# buttonInput.net
KiCad netlist of a schematic drawn in Altium Designer
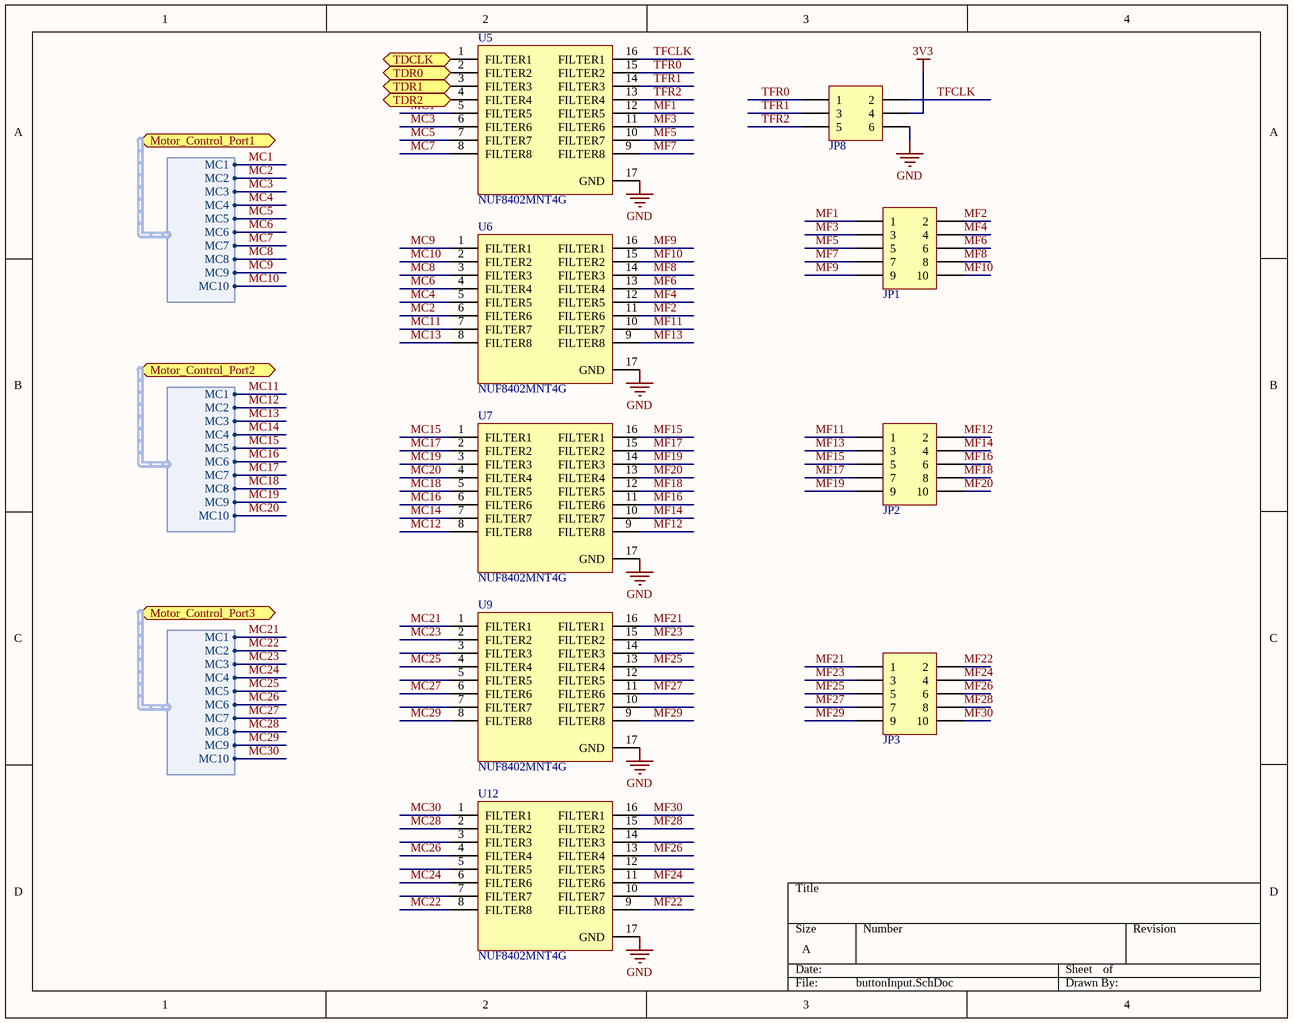
[diagram p0: buttonInput.SchDoc]

(export (version "E")
  (design (tool "Eeschema 10.0.6"))
  (components
    (comp (ref "JP1")
      (value "Header 5x2 2.54mm")
      (footprint "2X5")
      (description "Header, 8-Pin")
      (libsource (lib "HSBNE-Vend") (part "Header 5x2"))
    )
    (comp (ref "JP2")
      (value "Header 5x2 2.54mm")
      (footprint "2X5")
      (description "Header, 8-Pin")
      (libsource (lib "HSBNE-Vend") (part "Header 5x2"))
    )
    (comp (ref "JP3")
      (value "Header 5x2 2.54mm")
      (footprint "2X5")
      (description "Header, 8-Pin")
      (libsource (lib "HSBNE-Vend") (part "Header 5x2"))
    )
    (comp (ref "JP8")
      (value "Header 3x2 2.54mm")
      (footprint "2X3")
      (description "Header, 6-Pin")
      (libsource (lib "HSBNE-Vend") (part "Header 3x2"))
    )
    (comp (ref "U5")
      (value "NUF8402MNT4G")
      (footprint "ONSC-DFN-16-506AC_V")
      (fields (field (name "MANUFACTURER") "On Semiconductor"))
      (libsource (lib "Altium Content Vault") (part "ONSC-EMI-NUF8XXX-16"))
    )
    (comp (ref "U6")
      (value "NUF8402MNT4G")
      (footprint "ONSC-DFN-16-506AC_V")
      (fields (field (name "MANUFACTURER") "On Semiconductor"))
      (libsource (lib "Altium Content Vault") (part "ONSC-EMI-NUF8XXX-16"))
    )
    (comp (ref "U7")
      (value "NUF8402MNT4G")
      (footprint "ONSC-DFN-16-506AC_V")
      (fields (field (name "MANUFACTURER") "On Semiconductor"))
      (libsource (lib "Altium Content Vault") (part "ONSC-EMI-NUF8XXX-16"))
    )
    (comp (ref "U9")
      (value "NUF8402MNT4G")
      (footprint "ONSC-DFN-16-506AC_V")
      (fields (field (name "MANUFACTURER") "On Semiconductor"))
      (libsource (lib "Altium Content Vault") (part "ONSC-EMI-NUF8XXX-16"))
    )
    (comp (ref "U12")
      (value "NUF8402MNT4G")
      (footprint "ONSC-DFN-16-506AC_V")
      (fields (field (name "MANUFACTURER") "On Semiconductor"))
      (libsource (lib "Altium Content Vault") (part "ONSC-EMI-NUF8XXX-16"))
    )
  )
  (nets
    (net (code "2") (name "/MC1") (class "Default")
      (node (ref "U5") (pin "5") (pinfunction "FILTER5_5") (pintype "passive"))
    )
    (net (code "3") (name "/MC2") (class "Default")
      (node (ref "U6") (pin "6") (pinfunction "FILTER6_6") (pintype "passive"))
    )
    (net (code "4") (name "/MC3") (class "Default")
      (node (ref "U5") (pin "6") (pinfunction "FILTER6_6") (pintype "passive"))
    )
    (net (code "5") (name "/MC4") (class "Default")
      (node (ref "U6") (pin "5") (pinfunction "FILTER5_5") (pintype "passive"))
    )
    (net (code "6") (name "/MC5") (class "Default")
      (node (ref "U5") (pin "7") (pinfunction "FILTER7_7") (pintype "passive"))
    )
    (net (code "7") (name "/MC6") (class "Default")
      (node (ref "U6") (pin "4") (pinfunction "FILTER4_4") (pintype "passive"))
    )
    (net (code "8") (name "/MC7") (class "Default")
      (node (ref "U5") (pin "8") (pinfunction "FILTER8_8") (pintype "passive"))
    )
    (net (code "9") (name "/MC8") (class "Default")
      (node (ref "U6") (pin "3") (pinfunction "FILTER3_3") (pintype "passive"))
    )
    (net (code "10") (name "/MC9") (class "Default")
      (node (ref "U6") (pin "1") (pinfunction "FILTER1_1") (pintype "passive"))
    )
    (net (code "11") (name "/MC10") (class "Default")
      (node (ref "U6") (pin "2") (pinfunction "FILTER2_2") (pintype "passive"))
    )
    (net (code "12") (name "/MC11") (class "Default")
      (node (ref "U6") (pin "7") (pinfunction "FILTER7_7") (pintype "passive"))
    )
    (net (code "13") (name "/MC12") (class "Default")
      (node (ref "U7") (pin "8") (pinfunction "FILTER8_8") (pintype "passive"))
    )
    (net (code "14") (name "/MC13") (class "Default")
      (node (ref "U6") (pin "8") (pinfunction "FILTER8_8") (pintype "passive"))
    )
    (net (code "15") (name "/MC14") (class "Default")
      (node (ref "U7") (pin "7") (pinfunction "FILTER7_7") (pintype "passive"))
    )
    (net (code "16") (name "/MC15") (class "Default")
      (node (ref "U7") (pin "1") (pinfunction "FILTER1_1") (pintype "passive"))
    )
    (net (code "17") (name "/MC16") (class "Default")
      (node (ref "U7") (pin "6") (pinfunction "FILTER6_6") (pintype "passive"))
    )
    (net (code "18") (name "/MC17") (class "Default")
      (node (ref "U7") (pin "2") (pinfunction "FILTER2_2") (pintype "passive"))
    )
    (net (code "19") (name "/MC18") (class "Default")
      (node (ref "U7") (pin "5") (pinfunction "FILTER5_5") (pintype "passive"))
    )
    (net (code "20") (name "/MC19") (class "Default")
      (node (ref "U7") (pin "3") (pinfunction "FILTER3_3") (pintype "passive"))
    )
    (net (code "21") (name "/MC20") (class "Default")
      (node (ref "U7") (pin "4") (pinfunction "FILTER4_4") (pintype "passive"))
    )
    (net (code "22") (name "/MC21") (class "Default")
      (node (ref "U9") (pin "1") (pinfunction "FILTER1_1") (pintype "passive"))
    )
    (net (code "23") (name "/MC22") (class "Default")
      (node (ref "U12") (pin "8") (pinfunction "FILTER8_8") (pintype "passive"))
    )
    (net (code "24") (name "/MC23") (class "Default")
      (node (ref "U9") (pin "2") (pinfunction "FILTER2_2") (pintype "passive"))
    )
    (net (code "25") (name "/MC24") (class "Default")
      (node (ref "U12") (pin "6") (pinfunction "FILTER6_6") (pintype "passive"))
    )
    (net (code "26") (name "/MC25") (class "Default")
      (node (ref "U9") (pin "4") (pinfunction "FILTER4_4") (pintype "passive"))
    )
    (net (code "27") (name "/MC26") (class "Default")
      (node (ref "U12") (pin "4") (pinfunction "FILTER4_4") (pintype "passive"))
    )
    (net (code "28") (name "/MC27") (class "Default")
      (node (ref "U9") (pin "6") (pinfunction "FILTER6_6") (pintype "passive"))
    )
    (net (code "29") (name "/MC28") (class "Default")
      (node (ref "U12") (pin "2") (pinfunction "FILTER2_2") (pintype "passive"))
    )
    (net (code "30") (name "/MC29") (class "Default")
      (node (ref "U9") (pin "8") (pinfunction "FILTER8_8") (pintype "passive"))
    )
    (net (code "31") (name "/MC30") (class "Default")
      (node (ref "U12") (pin "1") (pinfunction "FILTER1_1") (pintype "passive"))
    )
    (net (code "32") (name "/MF1") (class "Default")
      (node (ref "JP1") (pin "1") (pinfunction "1_1") (pintype "passive"))
      (node (ref "U5") (pin "12") (pinfunction "FILTER5_12") (pintype "passive"))
    )
    (net (code "33") (name "/MF2") (class "Default")
      (node (ref "JP1") (pin "2") (pinfunction "2_2") (pintype "passive"))
      (node (ref "U6") (pin "11") (pinfunction "FILTER6_11") (pintype "passive"))
    )
    (net (code "34") (name "/MF3") (class "Default")
      (node (ref "JP1") (pin "3") (pinfunction "3_3") (pintype "passive"))
      (node (ref "U5") (pin "11") (pinfunction "FILTER6_11") (pintype "passive"))
    )
    (net (code "35") (name "/MF4") (class "Default")
      (node (ref "JP1") (pin "4") (pinfunction "4_4") (pintype "passive"))
      (node (ref "U6") (pin "12") (pinfunction "FILTER5_12") (pintype "passive"))
    )
    (net (code "36") (name "/MF5") (class "Default")
      (node (ref "JP1") (pin "5") (pinfunction "5_5") (pintype "passive"))
      (node (ref "U5") (pin "10") (pinfunction "FILTER7_10") (pintype "passive"))
    )
    (net (code "37") (name "/MF6") (class "Default")
      (node (ref "JP1") (pin "6") (pinfunction "6_6") (pintype "passive"))
      (node (ref "U6") (pin "13") (pinfunction "FILTER4_13") (pintype "passive"))
    )
    (net (code "38") (name "/MF7") (class "Default")
      (node (ref "JP1") (pin "7") (pinfunction "7_7") (pintype "passive"))
      (node (ref "U5") (pin "9") (pinfunction "FILTER8_9") (pintype "passive"))
    )
    (net (code "39") (name "/MF8") (class "Default")
      (node (ref "JP1") (pin "8") (pinfunction "8_8") (pintype "passive"))
      (node (ref "U6") (pin "14") (pinfunction "FILTER3_14") (pintype "passive"))
    )
    (net (code "40") (name "/MF9") (class "Default")
      (node (ref "JP1") (pin "9") (pinfunction "9_9") (pintype "passive"))
      (node (ref "U6") (pin "16") (pinfunction "FILTER1_16") (pintype "passive"))
    )
    (net (code "41") (name "/MF10") (class "Default")
      (node (ref "JP1") (pin "10") (pinfunction "10_10") (pintype "passive"))
      (node (ref "U6") (pin "15") (pinfunction "FILTER2_15") (pintype "passive"))
    )
    (net (code "42") (name "/MF11") (class "Default")
      (node (ref "JP2") (pin "1") (pinfunction "1_1") (pintype "passive"))
      (node (ref "U6") (pin "10") (pinfunction "FILTER7_10") (pintype "passive"))
    )
    (net (code "43") (name "/MF12") (class "Default")
      (node (ref "JP2") (pin "2") (pinfunction "2_2") (pintype "passive"))
      (node (ref "U7") (pin "9") (pinfunction "FILTER8_9") (pintype "passive"))
    )
    (net (code "44") (name "/MF13") (class "Default")
      (node (ref "JP2") (pin "3") (pinfunction "3_3") (pintype "passive"))
      (node (ref "U6") (pin "9") (pinfunction "FILTER8_9") (pintype "passive"))
    )
    (net (code "45") (name "/MF14") (class "Default")
      (node (ref "JP2") (pin "4") (pinfunction "4_4") (pintype "passive"))
      (node (ref "U7") (pin "10") (pinfunction "FILTER7_10") (pintype "passive"))
    )
    (net (code "46") (name "/MF15") (class "Default")
      (node (ref "JP2") (pin "5") (pinfunction "5_5") (pintype "passive"))
      (node (ref "U7") (pin "16") (pinfunction "FILTER1_16") (pintype "passive"))
    )
    (net (code "47") (name "/MF16") (class "Default")
      (node (ref "JP2") (pin "6") (pinfunction "6_6") (pintype "passive"))
      (node (ref "U7") (pin "11") (pinfunction "FILTER6_11") (pintype "passive"))
    )
    (net (code "48") (name "/MF17") (class "Default")
      (node (ref "JP2") (pin "7") (pinfunction "7_7") (pintype "passive"))
      (node (ref "U7") (pin "15") (pinfunction "FILTER2_15") (pintype "passive"))
    )
    (net (code "49") (name "/MF18") (class "Default")
      (node (ref "JP2") (pin "8") (pinfunction "8_8") (pintype "passive"))
      (node (ref "U7") (pin "12") (pinfunction "FILTER5_12") (pintype "passive"))
    )
    (net (code "50") (name "/MF19") (class "Default")
      (node (ref "JP2") (pin "9") (pinfunction "9_9") (pintype "passive"))
      (node (ref "U7") (pin "14") (pinfunction "FILTER3_14") (pintype "passive"))
    )
    (net (code "51") (name "/MF20") (class "Default")
      (node (ref "JP2") (pin "10") (pinfunction "10_10") (pintype "passive"))
      (node (ref "U7") (pin "13") (pinfunction "FILTER4_13") (pintype "passive"))
    )
    (net (code "52") (name "/MF21") (class "Default")
      (node (ref "JP3") (pin "1") (pinfunction "1_1") (pintype "passive"))
      (node (ref "U9") (pin "16") (pinfunction "FILTER1_16") (pintype "passive"))
    )
    (net (code "53") (name "/MF22") (class "Default")
      (node (ref "JP3") (pin "2") (pinfunction "2_2") (pintype "passive"))
      (node (ref "U12") (pin "9") (pinfunction "FILTER8_9") (pintype "passive"))
    )
    (net (code "54") (name "/MF23") (class "Default")
      (node (ref "JP3") (pin "3") (pinfunction "3_3") (pintype "passive"))
      (node (ref "U9") (pin "15") (pinfunction "FILTER2_15") (pintype "passive"))
    )
    (net (code "55") (name "/MF24") (class "Default")
      (node (ref "JP3") (pin "4") (pinfunction "4_4") (pintype "passive"))
      (node (ref "U12") (pin "11") (pinfunction "FILTER6_11") (pintype "passive"))
    )
    (net (code "56") (name "/MF25") (class "Default")
      (node (ref "JP3") (pin "5") (pinfunction "5_5") (pintype "passive"))
      (node (ref "U9") (pin "13") (pinfunction "FILTER4_13") (pintype "passive"))
    )
    (net (code "57") (name "/MF26") (class "Default")
      (node (ref "JP3") (pin "6") (pinfunction "6_6") (pintype "passive"))
      (node (ref "U12") (pin "13") (pinfunction "FILTER4_13") (pintype "passive"))
    )
    (net (code "58") (name "/MF27") (class "Default")
      (node (ref "JP3") (pin "7") (pinfunction "7_7") (pintype "passive"))
      (node (ref "U9") (pin "11") (pinfunction "FILTER6_11") (pintype "passive"))
    )
    (net (code "59") (name "/MF28") (class "Default")
      (node (ref "JP3") (pin "8") (pinfunction "8_8") (pintype "passive"))
      (node (ref "U12") (pin "15") (pinfunction "FILTER2_15") (pintype "passive"))
    )
    (net (code "60") (name "/MF29") (class "Default")
      (node (ref "JP3") (pin "9") (pinfunction "9_9") (pintype "passive"))
      (node (ref "U9") (pin "9") (pinfunction "FILTER8_9") (pintype "passive"))
    )
    (net (code "61") (name "/MF30") (class "Default")
      (node (ref "JP3") (pin "10") (pinfunction "10_10") (pintype "passive"))
      (node (ref "U12") (pin "16") (pinfunction "FILTER1_16") (pintype "passive"))
    )
    (net (code "62") (name "/TDCLK") (class "Default")
      (node (ref "U5") (pin "1") (pinfunction "FILTER1_1") (pintype "passive"))
    )
    (net (code "63") (name "/TDR0") (class "Default")
      (node (ref "U5") (pin "2") (pinfunction "FILTER2_2") (pintype "passive"))
    )
    (net (code "64") (name "/TDR1") (class "Default")
      (node (ref "U5") (pin "3") (pinfunction "FILTER3_3") (pintype "passive"))
    )
    (net (code "65") (name "/TDR2") (class "Default")
      (node (ref "U5") (pin "4") (pinfunction "FILTER4_4") (pintype "passive"))
    )
    (net (code "66") (name "/TFCLK") (class "Default")
      (node (ref "JP8") (pin "2") (pinfunction "2_2") (pintype "passive"))
      (node (ref "U5") (pin "16") (pinfunction "FILTER1_16") (pintype "passive"))
    )
    (net (code "67") (name "/TFR0") (class "Default")
      (node (ref "JP8") (pin "1") (pinfunction "1_1") (pintype "passive"))
      (node (ref "U5") (pin "15") (pinfunction "FILTER2_15") (pintype "passive"))
    )
    (net (code "68") (name "/TFR1") (class "Default")
      (node (ref "JP8") (pin "3") (pinfunction "3_3") (pintype "passive"))
      (node (ref "U5") (pin "14") (pinfunction "FILTER3_14") (pintype "passive"))
    )
    (net (code "69") (name "/TFR2") (class "Default")
      (node (ref "JP8") (pin "5") (pinfunction "5_5") (pintype "passive"))
      (node (ref "U5") (pin "13") (pinfunction "FILTER4_13") (pintype "passive"))
    )
    (net (code "71") (name "3V3") (class "Default")
      (node (ref "JP8") (pin "4") (pinfunction "4_4") (pintype "passive"))
    )
    (net (code "72") (name "GND") (class "Default")
      (node (ref "JP8") (pin "6") (pinfunction "6_6") (pintype "passive"))
      (node (ref "U12") (pin "17") (pinfunction "GND_17") (pintype "power_in"))
      (node (ref "U5") (pin "17") (pinfunction "GND_17") (pintype "power_in"))
      (node (ref "U6") (pin "17") (pinfunction "GND_17") (pintype "power_in"))
      (node (ref "U7") (pin "17") (pinfunction "GND_17") (pintype "power_in"))
      (node (ref "U9") (pin "17") (pinfunction "GND_17") (pintype "power_in"))
    )
    (net (code "73") (name "unconnected-(U9-FILTER3-Pad3)") (class "Default")
      (node (ref "U9") (pin "3") (pinfunction "FILTER3_3") (pintype "passive"))
    )
    (net (code "74") (name "unconnected-(U9-FILTER3-Pad14)") (class "Default")
      (node (ref "U9") (pin "14") (pinfunction "FILTER3_14") (pintype "passive"))
    )
    (net (code "75") (name "unconnected-(U9-FILTER5-Pad5)") (class "Default")
      (node (ref "U9") (pin "5") (pinfunction "FILTER5_5") (pintype "passive"))
    )
    (net (code "76") (name "unconnected-(U9-FILTER5-Pad12)") (class "Default")
      (node (ref "U9") (pin "12") (pinfunction "FILTER5_12") (pintype "passive"))
    )
    (net (code "77") (name "unconnected-(U9-FILTER7-Pad7)") (class "Default")
      (node (ref "U9") (pin "7") (pinfunction "FILTER7_7") (pintype "passive"))
    )
    (net (code "78") (name "unconnected-(U9-FILTER7-Pad10)") (class "Default")
      (node (ref "U9") (pin "10") (pinfunction "FILTER7_10") (pintype "passive"))
    )
    (net (code "79") (name "unconnected-(U12-FILTER3-Pad3)") (class "Default")
      (node (ref "U12") (pin "3") (pinfunction "FILTER3_3") (pintype "passive"))
    )
    (net (code "80") (name "unconnected-(U12-FILTER3-Pad14)") (class "Default")
      (node (ref "U12") (pin "14") (pinfunction "FILTER3_14") (pintype "passive"))
    )
    (net (code "81") (name "unconnected-(U12-FILTER5-Pad5)") (class "Default")
      (node (ref "U12") (pin "5") (pinfunction "FILTER5_5") (pintype "passive"))
    )
    (net (code "82") (name "unconnected-(U12-FILTER5-Pad12)") (class "Default")
      (node (ref "U12") (pin "12") (pinfunction "FILTER5_12") (pintype "passive"))
    )
    (net (code "83") (name "unconnected-(U12-FILTER7-Pad7)") (class "Default")
      (node (ref "U12") (pin "7") (pinfunction "FILTER7_7") (pintype "passive"))
    )
    (net (code "84") (name "unconnected-(U12-FILTER7-Pad10)") (class "Default")
      (node (ref "U12") (pin "10") (pinfunction "FILTER7_10") (pintype "passive"))
    )
  )
)
